# kr2_1.net
KiCad netlist of a schematic drawn in Altium Designer
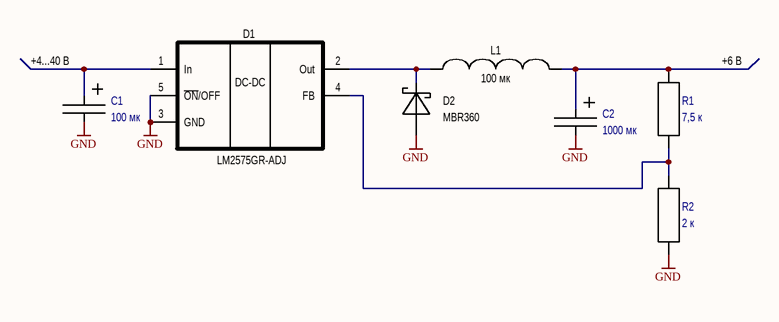
[diagram p0: kr2_1.SchDoc]

(export (version "E")
  (design (tool "Eeschema 10.0.6"))
  (components
    (comp (ref "C1")
      (value "100 мк")
      (fields (field (name "Comment") "100 мкФ ±* * * *, *"))
      (libsource (lib "STO") (part "C+"))
    )
    (comp (ref "C2")
      (value "1000 мк")
      (fields (field (name "Comment") "1000 мкФ ±* * * *, *"))
      (libsource (lib "STO") (part "C+"))
    )
    (comp (ref "D1") (value "LM2575GR-ADJ") (libsource (lib "STO") (part "LM2575GR-ADJ")))
    (comp (ref "D2") (value "MBR360") (libsource (lib "STO") (part "1N5821")))
    (comp (ref "L1") (value "100 мк") (libsource (lib "STO") (part "Inductor Sumida")))
    (comp (ref "R1")
      (value "7,5 к")
      (fields (field (name "Comment") "7,5 кОм ±* *, *"))
      (libsource (lib "STO") (part "R"))
    )
    (comp (ref "R2")
      (value "2 к")
      (fields (field (name "Comment") "2 кОм ±* *, *"))
      (libsource (lib "STO") (part "R"))
    )
  )
  (nets
    (net (code "1") (name "GND") (class "Default")
      (node (ref "C1") (pin "2") (pinfunction "2_2") (pintype "passive"))
      (node (ref "C2") (pin "2") (pinfunction "2_2") (pintype "passive"))
      (node (ref "D1") (pin "3") (pinfunction "GND_3") (pintype "passive"))
      (node (ref "D1") (pin "5") (pinfunction "~{ON}/OFF_5") (pintype "passive"))
      (node (ref "D2") (pin "1") (pinfunction "A_1") (pintype "passive"))
      (node (ref "R2") (pin "2") (pinfunction "2_2") (pintype "passive"))
    )
    (net (code "2") (name "Net-(C2-Pad1)") (class "Default")
      (node (ref "C2") (pin "1") (pinfunction "1_1") (pintype "passive"))
      (node (ref "R1") (pin "1") (pinfunction "1_1") (pintype "passive"))
    )
    (net (code "3") (name "Net-(D1-FB)") (class "Default")
      (node (ref "D1") (pin "4") (pinfunction "FB_4") (pintype "passive"))
      (node (ref "R1") (pin "2") (pinfunction "2_2") (pintype "passive"))
      (node (ref "R2") (pin "1") (pinfunction "1_1") (pintype "passive"))
    )
    (net (code "4") (name "Net-(D1-In)") (class "Default")
      (node (ref "C1") (pin "1") (pinfunction "1_1") (pintype "passive"))
      (node (ref "D1") (pin "1") (pinfunction "In_1") (pintype "passive"))
    )
    (net (code "5") (name "Net-(D1-Out)") (class "Default")
      (node (ref "D1") (pin "2") (pinfunction "Out_2") (pintype "passive"))
      (node (ref "D2") (pin "1") (pinfunction "C_1") (pintype "passive"))
    )
  )
)
